# Adder.net
KiCad netlist of a schematic drawn in Altium Designer
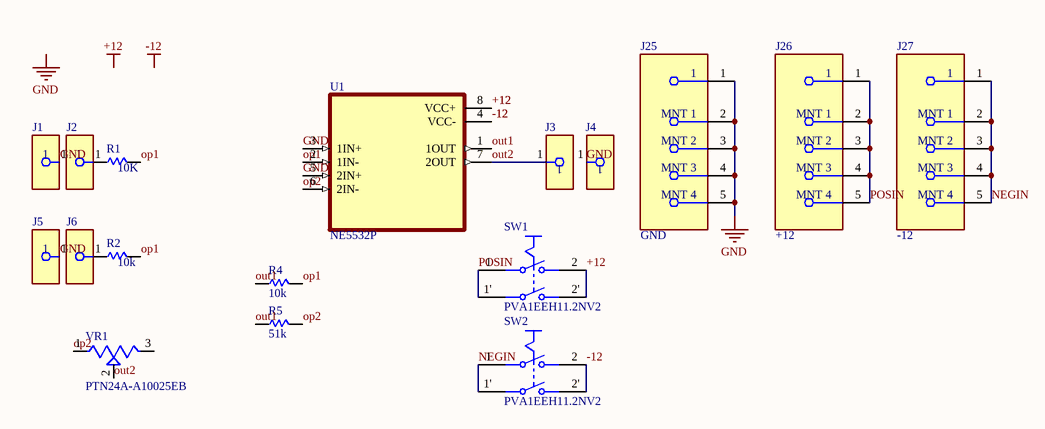
[diagram p0: Adder.SchDoc]

(export (version "E")
  (design (tool "Eeschema 10.0.6"))
  (components
    (comp (ref "J1")
      (value "~")
      (footprint "FP-1581-5-MFG")
      (description "CONN BANANA JACK TURRET GREEN")
      (libsource (lib "Schlib1") (part "CMP-73906-000011-1"))
    )
    (comp (ref "J2")
      (value "1581-5")
      (footprint "FP-1581-5-MFG")
      (description "CONN BANANA JACK TURRET GREEN")
      (libsource (lib "Schlib1") (part "CMP-73906-000011-1"))
    )
    (comp (ref "J3")
      (value "1581-5")
      (footprint "FP-1581-5-MFG")
      (description "CONN BANANA JACK TURRET GREEN")
      (libsource (lib "") (part "CMP-73906-000011-1_1"))
    )
    (comp (ref "J4")
      (value "1581-5")
      (footprint "FP-1581-5-MFG")
      (description "CONN BANANA JACK TURRET GREEN")
      (libsource (lib "") (part "CMP-73906-000011-1_1"))
    )
    (comp (ref "J5")
      (value "1581-5")
      (footprint "FP-1581-5-MFG")
      (description "CONN BANANA JACK TURRET GREEN")
      (libsource (lib "Schlib1") (part "CMP-73906-000011-1"))
    )
    (comp (ref "J6")
      (value "1581-5")
      (footprint "FP-1581-5-MFG")
      (description "CONN BANANA JACK TURRET GREEN")
      (libsource (lib "Schlib1") (part "CMP-73906-000011-1"))
    )
    (comp (ref "J25")
      (value "GND")
      (footprint "FP-FCR7350B-MFG")
      (description "4MM PANEL SKT S16N-PC BLACK")
      (libsource (lib "Altium Content Vault") (part "c65b8a639cdaef1819ea20b5466f8fa"))
    )
    (comp (ref "J26")
      (value "+12")
      (footprint "FP-FCR7350B-MFG")
      (description "4MM PANEL SKT S16N-PC BLACK")
      (libsource (lib "Altium Content Vault") (part "c65b8a639cdaef1819ea20b5466f8fa"))
    )
    (comp (ref "J27")
      (value "-12")
      (footprint "FP-FCR7350B-MFG")
      (description "4MM PANEL SKT S16N-PC BLACK")
      (libsource (lib "Altium Content Vault") (part "c65b8a639cdaef1819ea20b5466f8fa"))
    )
    (comp (ref "R1")
      (value "10K")
      (footprint "RESAD1100W55L680D260")
      (description "1.07 kOhms Â±1% 0.25W, 1/4W Through Hole Resistor Axial - Metal Film")
      (fields (field (name "MF") "Yageo") (field (name "MP") "MFR-25FBF52-1K"))
      (libsource (lib "Schlib1") (part "MFR-25FBF52-1K"))
    )
    (comp (ref "R2")
      (value "10k")
      (footprint "RESAD1100W55L680D260")
      (description "1.07 kOhms Â±1% 0.25W, 1/4W Through Hole Resistor Axial - Metal Film")
      (fields (field (name "MF") "Yageo") (field (name "MP") "MFR-25FBF52-1K"))
      (libsource (lib "Schlib1") (part "MFR-25FBF52-1K"))
    )
    (comp (ref "R4")
      (value "10k")
      (footprint "RESAD1100W55L680D260")
      (description "1.07 kOhms Â±1% 0.25W, 1/4W Through Hole Resistor Axial - Metal Film")
      (fields (field (name "MF") "Yageo") (field (name "MP") "MFR-25FBF52-1K"))
      (libsource (lib "Schlib1") (part "MFR-25FBF52-1K"))
    )
    (comp (ref "R5")
      (value "51k")
      (footprint "RESAD1100W55L680D260")
      (description "1.07 kOhms Â±1% 0.25W, 1/4W Through Hole Resistor Axial - Metal Film")
      (fields (field (name "MF") "Yageo") (field (name "MP") "MFR-25FBF52-1K"))
      (libsource (lib "Schlib1") (part "MFR-25FBF52-1K"))
    )
    (comp (ref "SW1")
      (value "PVA1EEH11.2NV2")
      (footprint "FP-PVA1EEH11_2NV2-MFG")
      (description "SWITCH PUSH DPST 0.1A 32V")
      (libsource (lib "Schlib1") (part "CMP-10035-000009-1"))
    )
    (comp (ref "SW2")
      (value "PVA1EEH11.2NV2")
      (footprint "FP-PVA1EEH11_2NV2-MFG")
      (description "SWITCH PUSH DPST 0.1A 32V")
      (libsource (lib "Schlib1") (part "CMP-10035-000009-1"))
    )
    (comp (ref "U1")
      (value "NE5532P")
      (footprint "DIP794W45P254L959H508Q8")
      (description "Dual, 30-V, 10-MHz, low-noise operational amplifier for audio applications")
      (fields (field (name "MF") "Texas Instruments"))
      (libsource (lib "Schlib1") (part "NE5532P"))
    )
    (comp (ref "VR1")
      (value "PTN24A-A10025EB")
      (footprint "TRIM_PTN24A-A10025EB")
      (description "100k Ohm 1 Gang Linear Panel Mount Potentiometer 1.0 Turns Carbon 0.5W, 1/2W PC Pins")
      (fields (field (name "MF") "Same Sky"))
      (libsource (lib "Schlib1") (part "PTN24A-A10025EB"))
    )
  )
  (nets
    (net (code "1") (name "+12") (class "Default")
      (node (ref "SW1") (pin "2") (pinfunction "2_2") (pintype "passive"))
      (node (ref "SW1") (pin "2'") (pinfunction "2'_2'") (pintype "passive"))
      (node (ref "U1") (pin "8") (pinfunction "VCC+_8") (pintype "power_in"))
    )
    (net (code "2") (name "-12") (class "Default")
      (node (ref "SW2") (pin "2") (pinfunction "2_2") (pintype "passive"))
      (node (ref "SW2") (pin "2'") (pinfunction "2'_2'") (pintype "passive"))
      (node (ref "U1") (pin "4") (pinfunction "VCC-_4") (pintype "power_in"))
    )
    (net (code "4") (name "/NEGIN") (class "Default")
      (node (ref "J27") (pin "1") (pinfunction "1_1") (pintype "passive"))
      (node (ref "J27") (pin "2") (pinfunction "MNT_1_2") (pintype "passive"))
      (node (ref "J27") (pin "3") (pinfunction "MNT_2_3") (pintype "passive"))
      (node (ref "J27") (pin "4") (pinfunction "MNT_3_4") (pintype "passive"))
      (node (ref "J27") (pin "5") (pinfunction "MNT_4_5") (pintype "passive"))
      (node (ref "SW2") (pin "1") (pinfunction "1_1") (pintype "passive"))
      (node (ref "SW2") (pin "1'") (pinfunction "1'_1'") (pintype "passive"))
    )
    (net (code "5") (name "/POSIN") (class "Default")
      (node (ref "J26") (pin "1") (pinfunction "1_1") (pintype "passive"))
      (node (ref "J26") (pin "2") (pinfunction "MNT_1_2") (pintype "passive"))
      (node (ref "J26") (pin "3") (pinfunction "MNT_2_3") (pintype "passive"))
      (node (ref "J26") (pin "4") (pinfunction "MNT_3_4") (pintype "passive"))
      (node (ref "J26") (pin "5") (pinfunction "MNT_4_5") (pintype "passive"))
      (node (ref "SW1") (pin "1") (pinfunction "1_1") (pintype "passive"))
      (node (ref "SW1") (pin "1'") (pinfunction "1'_1'") (pintype "passive"))
    )
    (net (code "6") (name "/op1") (class "Default")
      (node (ref "R1") (pin "2") (pinfunction "2_2") (pintype "passive"))
      (node (ref "R2") (pin "2") (pinfunction "2_2") (pintype "passive"))
      (node (ref "R4") (pin "2") (pinfunction "2_2") (pintype "passive"))
      (node (ref "U1") (pin "2") (pinfunction "1IN-_2") (pintype "input"))
    )
    (net (code "7") (name "/op2") (class "Default")
      (node (ref "R5") (pin "2") (pinfunction "2_2") (pintype "passive"))
      (node (ref "U1") (pin "6") (pinfunction "2IN-_6") (pintype "input"))
      (node (ref "VR1") (pin "1") (pinfunction "1_1") (pintype "passive"))
    )
    (net (code "8") (name "/out1") (class "Default")
      (node (ref "R4") (pin "1") (pinfunction "1_1") (pintype "passive"))
      (node (ref "R5") (pin "1") (pinfunction "1_1") (pintype "passive"))
      (node (ref "U1") (pin "1") (pinfunction "1OUT_1") (pintype "output"))
    )
    (net (code "9") (name "/out2") (class "Default")
      (node (ref "J3") (pin "1") (pinfunction "1_1") (pintype "passive"))
      (node (ref "U1") (pin "7") (pinfunction "2OUT_7") (pintype "output"))
      (node (ref "VR1") (pin "2") (pinfunction "2_2") (pintype "passive"))
    )
    (net (code "10") (name "GND") (class "Default")
      (node (ref "J1") (pin "1") (pinfunction "1_1") (pintype "passive"))
      (node (ref "J25") (pin "1") (pinfunction "1_1") (pintype "passive"))
      (node (ref "J25") (pin "2") (pinfunction "MNT_1_2") (pintype "passive"))
      (node (ref "J25") (pin "3") (pinfunction "MNT_2_3") (pintype "passive"))
      (node (ref "J25") (pin "4") (pinfunction "MNT_3_4") (pintype "passive"))
      (node (ref "J25") (pin "5") (pinfunction "MNT_4_5") (pintype "passive"))
      (node (ref "J4") (pin "1") (pinfunction "1_1") (pintype "passive"))
      (node (ref "J5") (pin "1") (pinfunction "1_1") (pintype "passive"))
      (node (ref "U1") (pin "3") (pinfunction "1IN+_3") (pintype "input"))
      (node (ref "U1") (pin "5") (pinfunction "2IN+_5") (pintype "input"))
    )
    (net (code "11") (name "Net-(J2-Pad1)") (class "Default")
      (node (ref "J2") (pin "1") (pinfunction "1_1") (pintype "passive"))
      (node (ref "R1") (pin "1") (pinfunction "1_1") (pintype "passive"))
    )
    (net (code "12") (name "Net-(J6-Pad1)") (class "Default")
      (node (ref "J6") (pin "1") (pinfunction "1_1") (pintype "passive"))
      (node (ref "R2") (pin "1") (pinfunction "1_1") (pintype "passive"))
    )
    (net (code "13") (name "unconnected-(VR1-Pad3)") (class "Default")
      (node (ref "VR1") (pin "3") (pinfunction "3_3") (pintype "passive"))
    )
  )
)
